# rc-gen.net
KiCad netlist of a schematic drawn in Altium Designer
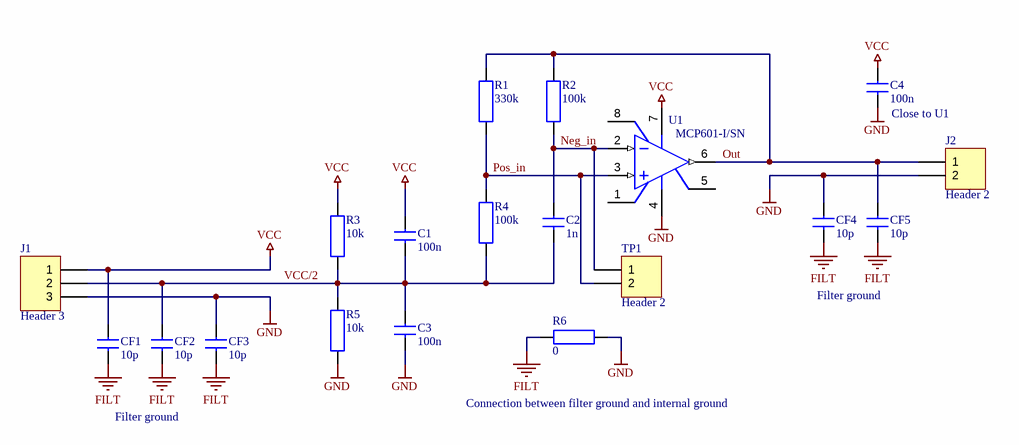
[diagram p0: rc-gen.SchDoc]

(export (version "E")
  (design (tool "Eeschema 10.0.6"))
  (components
    (comp (ref "C1")
      (value "100n")
      (footprint "0805")
      (description "Normaler Kondensator")
      (libsource (lib "DEVICE_HSLU") (part "C?"))
    )
    (comp (ref "C2")
      (value "1n")
      (footprint "0805")
      (description "Normaler Kondensator")
      (libsource (lib "DEVICE_HSLU") (part "C?"))
    )
    (comp (ref "C3")
      (value "100n")
      (footprint "0805")
      (description "Normaler Kondensator")
      (libsource (lib "DEVICE_HSLU") (part "C?"))
    )
    (comp (ref "C4")
      (value "100n")
      (footprint "0805")
      (description "Normaler Kondensator")
      (libsource (lib "DEVICE_HSLU") (part "C?"))
    )
    (comp (ref "CF1")
      (value "10p")
      (footprint "0805")
      (description "Normaler Kondensator")
      (libsource (lib "DEVICE_HSLU") (part "C?"))
    )
    (comp (ref "CF2")
      (value "10p")
      (footprint "0805")
      (description "Normaler Kondensator")
      (libsource (lib "DEVICE_HSLU") (part "C?"))
    )
    (comp (ref "CF3")
      (value "10p")
      (footprint "0805")
      (description "Normaler Kondensator")
      (libsource (lib "DEVICE_HSLU") (part "C?"))
    )
    (comp (ref "CF4")
      (value "10p")
      (footprint "0805")
      (description "Normaler Kondensator")
      (libsource (lib "DEVICE_HSLU") (part "C?"))
    )
    (comp (ref "CF5")
      (value "10p")
      (footprint "0805")
      (description "Normaler Kondensator")
      (libsource (lib "DEVICE_HSLU") (part "C?"))
    )
    (comp (ref "J1")
      (value "Header 3")
      (footprint "HDR1X3")
      (description "Header, 3-Pin")
      (fields (field (name "PUBLISHER") "Altium Limited"))
      (libsource (lib "Miscellaneous Connectors") (part "Header 3"))
    )
    (comp (ref "J2")
      (value "Header 2")
      (footprint "HDR1X2")
      (description "Header, 2-Pin")
      (fields (field (name "PUBLISHER") "Altium Limited"))
      (libsource (lib "Miscellaneous Connectors") (part "Header 2"))
    )
    (comp (ref "R1")
      (value "330k")
      (footprint "0805")
      (description "Normaler Widerstand")
      (libsource (lib "DEVICE_HSLU") (part "R?"))
    )
    (comp (ref "R2")
      (value "100k")
      (footprint "0805")
      (description "Normaler Widerstand")
      (libsource (lib "DEVICE_HSLU") (part "R?"))
    )
    (comp (ref "R3")
      (value "10k")
      (footprint "0805")
      (description "Normaler Widerstand")
      (libsource (lib "DEVICE_HSLU") (part "R?"))
    )
    (comp (ref "R4")
      (value "100k")
      (footprint "0805")
      (description "Normaler Widerstand")
      (libsource (lib "DEVICE_HSLU") (part "R?"))
    )
    (comp (ref "R5")
      (value "10k")
      (footprint "0805")
      (description "Normaler Widerstand")
      (libsource (lib "DEVICE_HSLU") (part "R?"))
    )
    (comp (ref "R6")
      (value "0")
      (footprint "0805")
      (description "Normaler Widerstand")
      (libsource (lib "DEVICE_HSLU") (part "R?"))
    )
    (comp (ref "TP1")
      (value "Header 2")
      (footprint "HDR1X2")
      (description "Header, 2-Pin")
      (fields (field (name "PUBLISHER") "Altium Limited"))
      (libsource (lib "Miscellaneous Connectors") (part "Header 2"))
    )
    (comp (ref "U1")
      (value "MCP601-I/SN")
      (footprint "SOIC-SN8_N")
      (description "2.7V to 6.0V Single Supply CMOS Operational Amplifier, 8-Pin SOIC, Industrial Temperature")
      (fields (field (name "PUBLISHER") "Altium Limited"))
      (libsource (lib "Microchip Linear Devices") (part "MCP601-I/SN"))
    )
  )
  (nets
    (net (code "1") (name "/Neg_in") (class "Default")
      (node (ref "C2") (pin "1") (pinfunction "1_1") (pintype "passive"))
      (node (ref "R2") (pin "1") (pintype "passive"))
      (node (ref "TP1") (pin "1") (pinfunction "1_1") (pintype "passive"))
      (node (ref "U1") (pin "2") (pinfunction "VIN-_2") (pintype "input"))
    )
    (net (code "2") (name "/Out") (class "Default")
      (node (ref "CF5") (pin "1") (pinfunction "1_1") (pintype "passive"))
      (node (ref "J2") (pin "1") (pinfunction "1_1") (pintype "passive"))
      (node (ref "R1") (pin "2") (pintype "passive"))
      (node (ref "R2") (pin "2") (pintype "passive"))
      (node (ref "U1") (pin "6") (pinfunction "VOUT_6") (pintype "output"))
    )
    (net (code "3") (name "/Pos_in") (class "Default")
      (node (ref "R1") (pin "1") (pintype "passive"))
      (node (ref "R4") (pin "2") (pintype "passive"))
      (node (ref "TP1") (pin "2") (pinfunction "2_2") (pintype "passive"))
      (node (ref "U1") (pin "3") (pinfunction "VIN+_3") (pintype "input"))
    )
    (net (code "4") (name "/VCC{slash}2") (class "Default")
      (node (ref "C1") (pin "2") (pinfunction "2_2") (pintype "passive"))
      (node (ref "C2") (pin "2") (pinfunction "2_2") (pintype "passive"))
      (node (ref "C3") (pin "1") (pinfunction "1_1") (pintype "passive"))
      (node (ref "CF2") (pin "1") (pinfunction "1_1") (pintype "passive"))
      (node (ref "J1") (pin "2") (pinfunction "2_2") (pintype "passive"))
      (node (ref "R3") (pin "1") (pintype "passive"))
      (node (ref "R4") (pin "1") (pintype "passive"))
      (node (ref "R5") (pin "2") (pintype "passive"))
    )
    (net (code "5") (name "FILT") (class "Default")
      (node (ref "CF1") (pin "2") (pinfunction "2_2") (pintype "passive"))
      (node (ref "CF2") (pin "2") (pinfunction "2_2") (pintype "passive"))
      (node (ref "CF3") (pin "2") (pinfunction "2_2") (pintype "passive"))
      (node (ref "CF4") (pin "2") (pinfunction "2_2") (pintype "passive"))
      (node (ref "CF5") (pin "2") (pinfunction "2_2") (pintype "passive"))
      (node (ref "R6") (pin "1") (pintype "passive"))
    )
    (net (code "6") (name "GND") (class "Default")
      (node (ref "C3") (pin "2") (pinfunction "2_2") (pintype "passive"))
      (node (ref "C4") (pin "2") (pinfunction "2_2") (pintype "passive"))
      (node (ref "CF3") (pin "1") (pinfunction "1_1") (pintype "passive"))
      (node (ref "CF4") (pin "1") (pinfunction "1_1") (pintype "passive"))
      (node (ref "J1") (pin "3") (pinfunction "3_3") (pintype "passive"))
      (node (ref "J2") (pin "2") (pinfunction "2_2") (pintype "passive"))
      (node (ref "R5") (pin "1") (pintype "passive"))
      (node (ref "R6") (pin "2") (pintype "passive"))
      (node (ref "U1") (pin "4") (pinfunction "VSS_4") (pintype "power_in"))
    )
    (net (code "7") (name "VCC") (class "Default")
      (node (ref "C1") (pin "1") (pinfunction "1_1") (pintype "passive"))
      (node (ref "C4") (pin "1") (pinfunction "1_1") (pintype "passive"))
      (node (ref "CF1") (pin "1") (pinfunction "1_1") (pintype "passive"))
      (node (ref "J1") (pin "1") (pinfunction "1_1") (pintype "passive"))
      (node (ref "R3") (pin "2") (pintype "passive"))
      (node (ref "U1") (pin "7") (pinfunction "VDD_7") (pintype "power_in"))
    )
    (net (code "8") (name "unconnected-(U1-NC-Pad1)") (class "Default")
      (node (ref "U1") (pin "1") (pinfunction "NC_1") (pintype "passive"))
    )
    (net (code "9") (name "unconnected-(U1-NC-Pad5)") (class "Default")
      (node (ref "U1") (pin "5") (pinfunction "NC_5") (pintype "passive"))
    )
    (net (code "10") (name "unconnected-(U1-NC-Pad8)") (class "Default")
      (node (ref "U1") (pin "8") (pinfunction "NC_8") (pintype "passive"))
    )
  )
)
